# miniSpinac.net
KiCad netlist of a schematic drawn in EAGLE
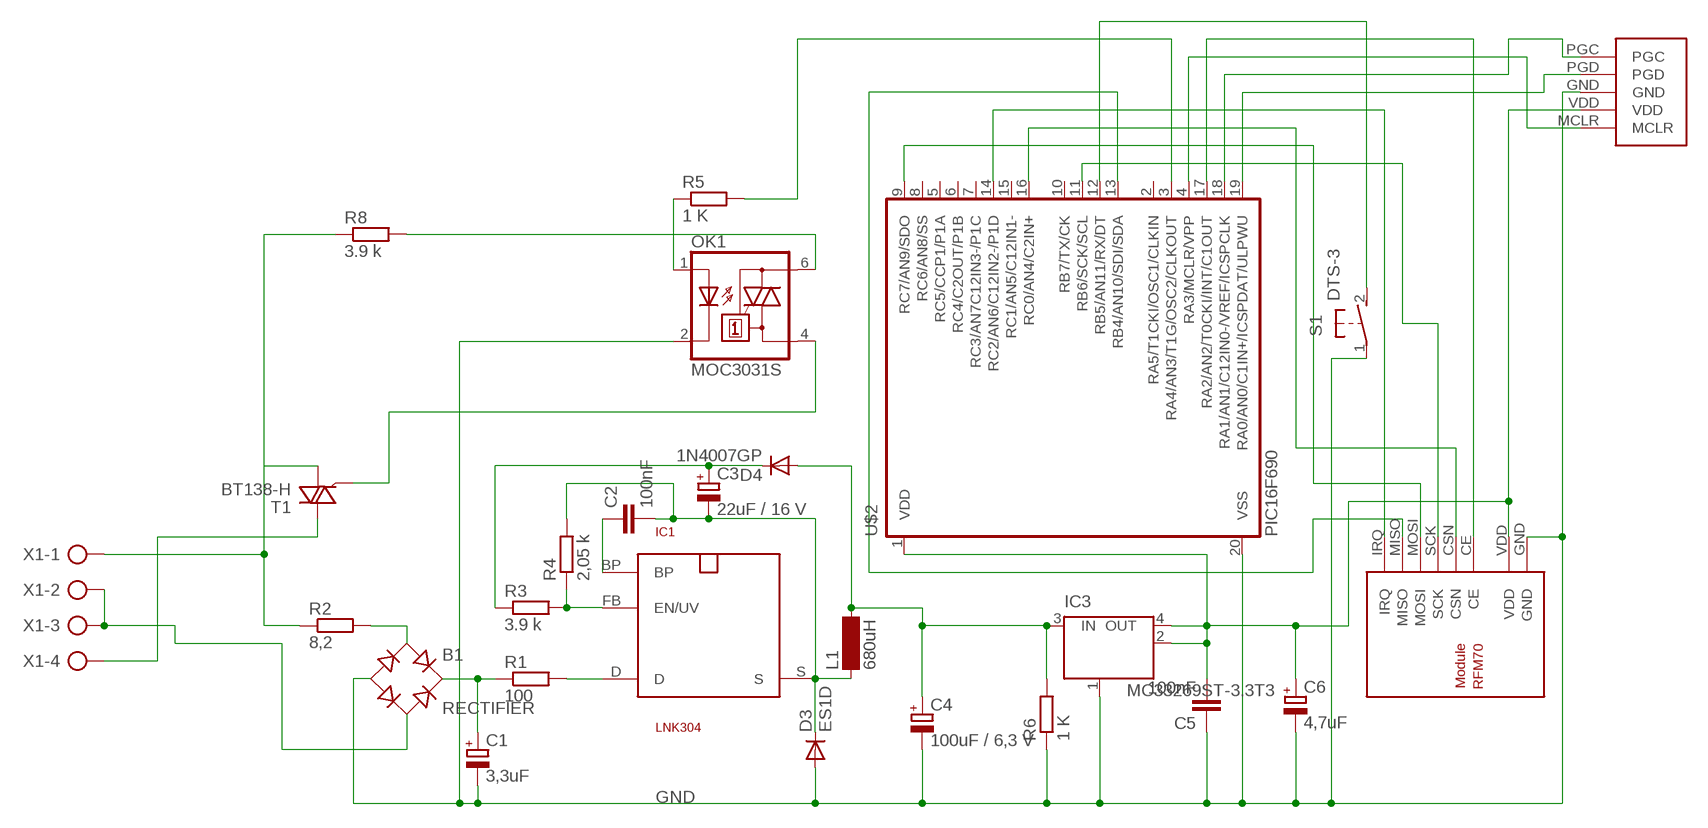
[diagram p0: schematic, sheet 1]

(export (version "E")
  (design (tool "Eeschema 10.0.6"))
  (components
    (comp (ref "B1")
      (value "RECTIFIER")
      (footprint "eagle-import:TO-269AA")
      (libsource (lib "eagle-import") (part "RECTIFIER-S40"))
    )
    (comp (ref "C1")
      (value "3,3uF")
      (footprint "eagle-import:E5-10,5")
      (libsource (lib "eagle-import") (part "CPOL-EUE5-10.5"))
    )
    (comp (ref "C2")
      (value "100nF")
      (footprint "eagle-import:C2012")
      (libsource (lib "eagle-import") (part "C-EUC2012"))
    )
    (comp (ref "C3")
      (value "22uF / 16 V")
      (footprint "eagle-import:SMC_C")
      (libsource (lib "eagle-import") (part "CPOL-EUSMCC"))
    )
    (comp (ref "C4")
      (value "100uF / 6,3 V")
      (footprint "eagle-import:E2,5-5")
      (libsource (lib "eagle-import") (part "CPOL-EUE2.5-5"))
    )
    (comp (ref "C5")
      (value "100nF")
      (footprint "eagle-import:C2012")
      (libsource (lib "eagle-import") (part "C-EUC2012"))
    )
    (comp (ref "C6")
      (value "4,7uF")
      (footprint "eagle-import:SMC_A")
      (libsource (lib "eagle-import") (part "CPOL-EUSMCA"))
    )
    (comp (ref "D3")
      (value "ES1D")
      (footprint "eagle-import:DO214AC")
      (libsource (lib "eagle-import") (part "DIODE-DO214AC"))
    )
    (comp (ref "D4")
      (value "1N4007GP")
      (footprint "eagle-import:DO214AA")
      (libsource (lib "eagle-import") (part "DIODE-DO214AA"))
    )
    (comp (ref "IC1")
      (value "LNK304")
      (footprint "eagle-import:SO-8C")
      (libsource (lib "eagle-import") (part "SO-8C"))
    )
    (comp (ref "IC3")
      (value "MC33269ST-3.3T3")
      (footprint "eagle-import:SOT223")
      (libsource (lib "eagle-import") (part "MC33269ST-3.3T3"))
    )
    (comp (ref "L1")
      (value "680uH")
      (footprint "eagle-import:BS11")
      (libsource (lib "eagle-import") (part "BS11"))
    )
    (comp (ref "OK1")
      (value "MOC3031S")
      (footprint "eagle-import:DIL6-SMD")
      (fields (field (name "MF") "FAIRCHILD SEMICONDUCTOR") (field (name "MPN") "MOC3031SM"))
      (libsource (lib "eagle-import") (part "MOC30S31"))
    )
    (comp (ref "R1")
      (value "100")
      (footprint "eagle-import:R2512W")
      (libsource (lib "eagle-import") (part "R-EU_R2512W"))
    )
    (comp (ref "R2")
      (value "8,2")
      (footprint "eagle-import:0411_12")
      (libsource (lib "eagle-import") (part "R-EU_0411/12"))
    )
    (comp (ref "R3")
      (value "3.9 k")
      (footprint "eagle-import:M2012")
      (libsource (lib "eagle-import") (part "R-EU_M2012"))
    )
    (comp (ref "R4")
      (value "2,05 k")
      (footprint "eagle-import:M2012")
      (libsource (lib "eagle-import") (part "R-EU_M2012"))
    )
    (comp (ref "R5")
      (value "1 K")
      (footprint "eagle-import:M2012")
      (libsource (lib "eagle-import") (part "R-EU_M2012"))
    )
    (comp (ref "R6")
      (value "1 K")
      (footprint "eagle-import:M2012")
      (libsource (lib "eagle-import") (part "R-EU_M2012"))
    )
    (comp (ref "R8")
      (value "3.9 k")
      (footprint "eagle-import:M2012")
      (libsource (lib "eagle-import") (part "R-EU_M2012"))
    )
    (comp (ref "S1")
      (value "DTS-3")
      (footprint "eagle-import:DTS-3")
      (libsource (lib "eagle-import") (part "DTS-3"))
    )
    (comp (ref "T1")
      (value "BT138-H")
      (footprint "eagle-import:TO220BH")
      (libsource (lib "eagle-import") (part "BT138-H"))
    )
    (comp (ref "U$1")
      (value "RFM70")
      (footprint "eagle-import:RFM70")
      (libsource (lib "eagle-import") (part "RFM70"))
    )
    (comp (ref "U$2")
      (value "PIC16F690")
      (footprint "eagle-import:SSOP20")
      (libsource (lib "eagle-import") (part "PIC16F690"))
    )
    (comp (ref "U$3")
      (value "PROGRAMMINGHEADERDIP")
      (footprint "eagle-import:PROGHEADER")
      (libsource (lib "eagle-import") (part "PROGRAMMINGHEADERDIP"))
    )
    (comp (ref "X1")
      (value "AK500/4")
      (footprint "eagle-import:AK500_4")
      (libsource (lib "eagle-import") (part "AK500/4"))
    )
  )
  (nets
    (net (code "1") (name "/GND") (class "Default")
      (node (ref "B1") (pin "-") (pinfunction "-_-") (pintype "passive"))
      (node (ref "C1") (pin "-") (pinfunction "-_-") (pintype "passive"))
      (node (ref "C4") (pin "-") (pinfunction "-_-") (pintype "passive"))
      (node (ref "C5") (pin "1") (pinfunction "1_1") (pintype "passive"))
      (node (ref "C6") (pin "-") (pinfunction "-_-") (pintype "passive"))
      (node (ref "D3") (pin "A") (pinfunction "A_A") (pintype "passive"))
      (node (ref "IC3") (pin "1") (pinfunction "GND/ADJ_1") (pintype "input"))
      (node (ref "OK1") (pin "2") (pinfunction "C_2") (pintype "passive"))
      (node (ref "R6") (pin "1") (pinfunction "1_1") (pintype "passive"))
      (node (ref "S1") (pin "1") (pinfunction "1_1") (pintype "passive"))
      (node (ref "U$1") (pin "GND") (pinfunction "GND_GND") (pintype "power_in"))
      (node (ref "U$2") (pin "20") (pinfunction "VSS_20") (pintype "power_in"))
      (node (ref "U$3") (pin "GND") (pinfunction "GND_GND") (pintype "power_in"))
    )
    (net (code "2") (name "Net-(B1-Pad+)") (class "Default")
      (node (ref "B1") (pin "+") (pinfunction "+_+") (pintype "passive"))
      (node (ref "C1") (pin "+") (pinfunction "+_+") (pintype "passive"))
      (node (ref "R1") (pin "1") (pinfunction "1_1") (pintype "passive"))
    )
    (net (code "3") (name "Net-(B1-PadAC1)") (class "Default")
      (node (ref "B1") (pin "AC1") (pinfunction "AC1_AC1") (pintype "passive"))
      (node (ref "R2") (pin "2") (pinfunction "2_2") (pintype "passive"))
    )
    (net (code "4") (name "Net-(C2-Pad1)") (class "Default")
      (node (ref "C2") (pin "1") (pinfunction "1_1") (pintype "passive"))
      (node (ref "IC1") (pin "BP") (pinfunction "BP_BP") (pintype "passive"))
    )
    (net (code "5") (name "Net-(C2-Pad2)") (class "Default")
      (node (ref "C2") (pin "2") (pinfunction "2_2") (pintype "passive"))
      (node (ref "C3") (pin "-") (pinfunction "-_-") (pintype "passive"))
      (node (ref "D3") (pin "C") (pinfunction "C_C") (pintype "passive"))
      (node (ref "IC1") (pin "S") (pinfunction "S_S") (pintype "power_in"))
      (node (ref "L1") (pin "1") (pinfunction "1_1") (pintype "passive"))
      (node (ref "R4") (pin "2") (pinfunction "2_2") (pintype "passive"))
    )
    (net (code "6") (name "Net-(C3-Pad+)") (class "Default")
      (node (ref "C3") (pin "+") (pinfunction "+_+") (pintype "passive"))
      (node (ref "D4") (pin "C") (pinfunction "C_C") (pintype "passive"))
      (node (ref "R3") (pin "1") (pinfunction "1_1") (pintype "passive"))
    )
    (net (code "7") (name "Net-(IC1-EN{slash}UV)") (class "Default")
      (node (ref "IC1") (pin "FB") (pinfunction "EN/UV_FB") (pintype "input"))
      (node (ref "R3") (pin "2") (pinfunction "2_2") (pintype "passive"))
      (node (ref "R4") (pin "1") (pinfunction "1_1") (pintype "passive"))
    )
    (net (code "8") (name "Net-(IC1-PadD)") (class "Default")
      (node (ref "IC1") (pin "D") (pinfunction "D_D") (pintype "open_collector"))
      (node (ref "R1") (pin "2") (pinfunction "2_2") (pintype "passive"))
    )
    (net (code "9") (name "Net-(IC3-IN)") (class "Default")
      (node (ref "C4") (pin "+") (pinfunction "+_+") (pintype "passive"))
      (node (ref "D4") (pin "A") (pinfunction "A_A") (pintype "passive"))
      (node (ref "IC3") (pin "3") (pinfunction "IN_3") (pintype "input"))
      (node (ref "L1") (pin "2") (pinfunction "2_2") (pintype "passive"))
      (node (ref "R6") (pin "2") (pinfunction "2_2") (pintype "passive"))
    )
    (net (code "10") (name "Net-(OK1-A)") (class "Default")
      (node (ref "OK1") (pin "1") (pinfunction "A_1") (pintype "passive"))
      (node (ref "R5") (pin "1") (pinfunction "1_1") (pintype "passive"))
    )
    (net (code "11") (name "Net-(OK1-A1)") (class "Default")
      (node (ref "OK1") (pin "4") (pinfunction "A1_4") (pintype "passive"))
      (node (ref "T1") (pin "G") (pinfunction "G_G") (pintype "passive"))
    )
    (net (code "12") (name "Net-(OK1-A2)") (class "Default")
      (node (ref "OK1") (pin "6") (pinfunction "A2_6") (pintype "passive"))
      (node (ref "R8") (pin "2") (pinfunction "2_2") (pintype "passive"))
    )
    (net (code "13") (name "Net-(T1-A1)") (class "Default")
      (node (ref "R2") (pin "1") (pinfunction "1_1") (pintype "passive"))
      (node (ref "R8") (pin "1") (pinfunction "1_1") (pintype "passive"))
      (node (ref "T1") (pin "T1") (pinfunction "A1_T1") (pintype "passive"))
      (node (ref "X1") (pin "1") (pinfunction "KL_1") (pintype "passive"))
    )
    (net (code "14") (name "Net-(T1-A2)") (class "Default")
      (node (ref "T1") (pin "T2") (pinfunction "A2_T2") (pintype "passive"))
      (node (ref "X1") (pin "4") (pinfunction "KL_4") (pintype "passive"))
    )
    (net (code "15") (name "Net-(U$2-RA0{slash}AN0{slash}C1IN+{slash}ICSPDAT{slash}ULPWU)") (class "Default")
      (node (ref "U$2") (pin "19") (pinfunction "RA0/AN0/C1IN+/ICSPDAT/ULPWU_19") (pintype "bidirectional"))
      (node (ref "U$3") (pin "PGD") (pinfunction "PGD_PGD") (pintype "bidirectional"))
    )
    (net (code "16") (name "Net-(U$2-RA1{slash}AN1{slash}C12IN0-{slash}VREF{slash}ICSPCLK)") (class "Default")
      (node (ref "U$2") (pin "18") (pinfunction "RA1/AN1/C12IN0-/VREF/ICSPCLK_18") (pintype "bidirectional"))
      (node (ref "U$3") (pin "PGC") (pinfunction "PGC_PGC") (pintype "bidirectional"))
    )
    (net (code "17") (name "Net-(U$2-RA2{slash}AN2{slash}T0CKI{slash}INT{slash}C1OUT)") (class "Default")
      (node (ref "U$1") (pin "CE") (pinfunction "CE_CE") (pintype "bidirectional"))
      (node (ref "U$2") (pin "17") (pinfunction "RA2/AN2/T0CKI/INT/C1OUT_17") (pintype "bidirectional"))
    )
    (net (code "18") (name "Net-(U$2-RA3{slash}MCLR{slash}VPP)") (class "Default")
      (node (ref "U$2") (pin "4") (pinfunction "RA3/MCLR/VPP_4") (pintype "bidirectional"))
      (node (ref "U$3") (pin "MCLR") (pinfunction "MCLR_MCLR") (pintype "output"))
    )
    (net (code "19") (name "Net-(U$2-RA4{slash}AN3{slash}T1G{slash}OSC2{slash}CLKOUT)") (class "Default")
      (node (ref "R5") (pin "2") (pinfunction "2_2") (pintype "passive"))
      (node (ref "U$2") (pin "3") (pinfunction "RA4/AN3/T1G/OSC2/CLKOUT_3") (pintype "bidirectional"))
    )
    (net (code "20") (name "Net-(U$2-RB4{slash}AN10{slash}SDI{slash}SDA)") (class "Default")
      (node (ref "U$1") (pin "MISO") (pinfunction "MISO_MISO") (pintype "bidirectional"))
      (node (ref "U$2") (pin "13") (pinfunction "RB4/AN10/SDI/SDA_13") (pintype "bidirectional"))
    )
    (net (code "21") (name "Net-(U$2-RB5{slash}AN11{slash}RX{slash}DT)") (class "Default")
      (node (ref "S1") (pin "2") (pinfunction "2_2") (pintype "passive"))
      (node (ref "U$2") (pin "12") (pinfunction "RB5/AN11/RX/DT_12") (pintype "bidirectional"))
    )
    (net (code "22") (name "Net-(U$2-RB6{slash}SCK{slash}SCL)") (class "Default")
      (node (ref "U$1") (pin "SCK") (pinfunction "SCK_SCK") (pintype "bidirectional"))
      (node (ref "U$2") (pin "11") (pinfunction "RB6/SCK/SCL_11") (pintype "bidirectional"))
    )
    (net (code "23") (name "Net-(U$2-RC0{slash}AN4{slash}C2IN+)") (class "Default")
      (node (ref "U$1") (pin "CSN") (pinfunction "CSN_CSN") (pintype "bidirectional"))
      (node (ref "U$2") (pin "16") (pinfunction "RC0/AN4/C2IN+_16") (pintype "bidirectional"))
    )
    (net (code "24") (name "Net-(U$2-RC2{slash}AN6{slash}C12IN2-{slash}P1D)") (class "Default")
      (node (ref "U$1") (pin "IRQ") (pinfunction "IRQ_IRQ") (pintype "bidirectional"))
      (node (ref "U$2") (pin "14") (pinfunction "RC2/AN6/C12IN2-/P1D_14") (pintype "bidirectional"))
    )
    (net (code "25") (name "Net-(U$2-RC7{slash}AN9{slash}SDO)") (class "Default")
      (node (ref "U$1") (pin "MOSI") (pinfunction "MOSI_MOSI") (pintype "bidirectional"))
      (node (ref "U$2") (pin "9") (pinfunction "RC7/AN9/SDO_9") (pintype "bidirectional"))
    )
    (net (code "26") (name "Net-(U$2-VDD)") (class "Default")
      (node (ref "C5") (pin "2") (pinfunction "2_2") (pintype "passive"))
      (node (ref "C6") (pin "+") (pinfunction "+_+") (pintype "passive"))
      (node (ref "IC3") (pin "2") (pinfunction "OUT_2") (pintype "passive"))
      (node (ref "IC3") (pin "4") (pinfunction "OUT_4") (pintype "passive"))
      (node (ref "U$1") (pin "VDD") (pinfunction "VDD_VDD") (pintype "power_in"))
      (node (ref "U$2") (pin "1") (pinfunction "VDD_1") (pintype "power_in"))
      (node (ref "U$3") (pin "VDD") (pinfunction "VDD_VDD") (pintype "power_in"))
    )
    (net (code "27") (name "Net-(X1B-KL)") (class "Default")
      (node (ref "B1") (pin "AC2") (pinfunction "AC2_AC2") (pintype "passive"))
      (node (ref "X1") (pin "2") (pinfunction "KL_2") (pintype "passive"))
      (node (ref "X1") (pin "3") (pinfunction "KL_3") (pintype "passive"))
    )
    (net (code "28") (name "unconnected-(U$2-RA5{slash}T1CKI{slash}OSC1{slash}CLKIN-Pad2)") (class "Default")
      (node (ref "U$2") (pin "2") (pinfunction "RA5/T1CKI/OSC1/CLKIN_2") (pintype "bidirectional"))
    )
    (net (code "29") (name "unconnected-(U$2-RB7{slash}TX{slash}CK-Pad10)") (class "Default")
      (node (ref "U$2") (pin "10") (pinfunction "RB7/TX/CK_10") (pintype "bidirectional"))
    )
    (net (code "30") (name "unconnected-(U$2-RC1{slash}AN5{slash}C12IN1--Pad15)") (class "Default")
      (node (ref "U$2") (pin "15") (pinfunction "RC1/AN5/C12IN1-_15") (pintype "bidirectional"))
    )
    (net (code "31") (name "unconnected-(U$2-RC3{slash}AN7C12IN3-{slash}P1C-Pad7)") (class "Default")
      (node (ref "U$2") (pin "7") (pinfunction "RC3/AN7C12IN3-/P1C_7") (pintype "bidirectional"))
    )
    (net (code "32") (name "unconnected-(U$2-RC4{slash}C2OUT{slash}P1B-Pad6)") (class "Default")
      (node (ref "U$2") (pin "6") (pinfunction "RC4/C2OUT/P1B_6") (pintype "bidirectional"))
    )
    (net (code "33") (name "unconnected-(U$2-RC5{slash}CCP1{slash}P1A-Pad5)") (class "Default")
      (node (ref "U$2") (pin "5") (pinfunction "RC5/CCP1/P1A_5") (pintype "bidirectional"))
    )
    (net (code "34") (name "unconnected-(U$2-RC6{slash}AN8{slash}SS-Pad8)") (class "Default")
      (node (ref "U$2") (pin "8") (pinfunction "RC6/AN8/SS_8") (pintype "bidirectional"))
    )
  )
)
